# Strathim_MCU_Pin_Plan.net
KiCad netlist of a schematic drawn in Altium Designer
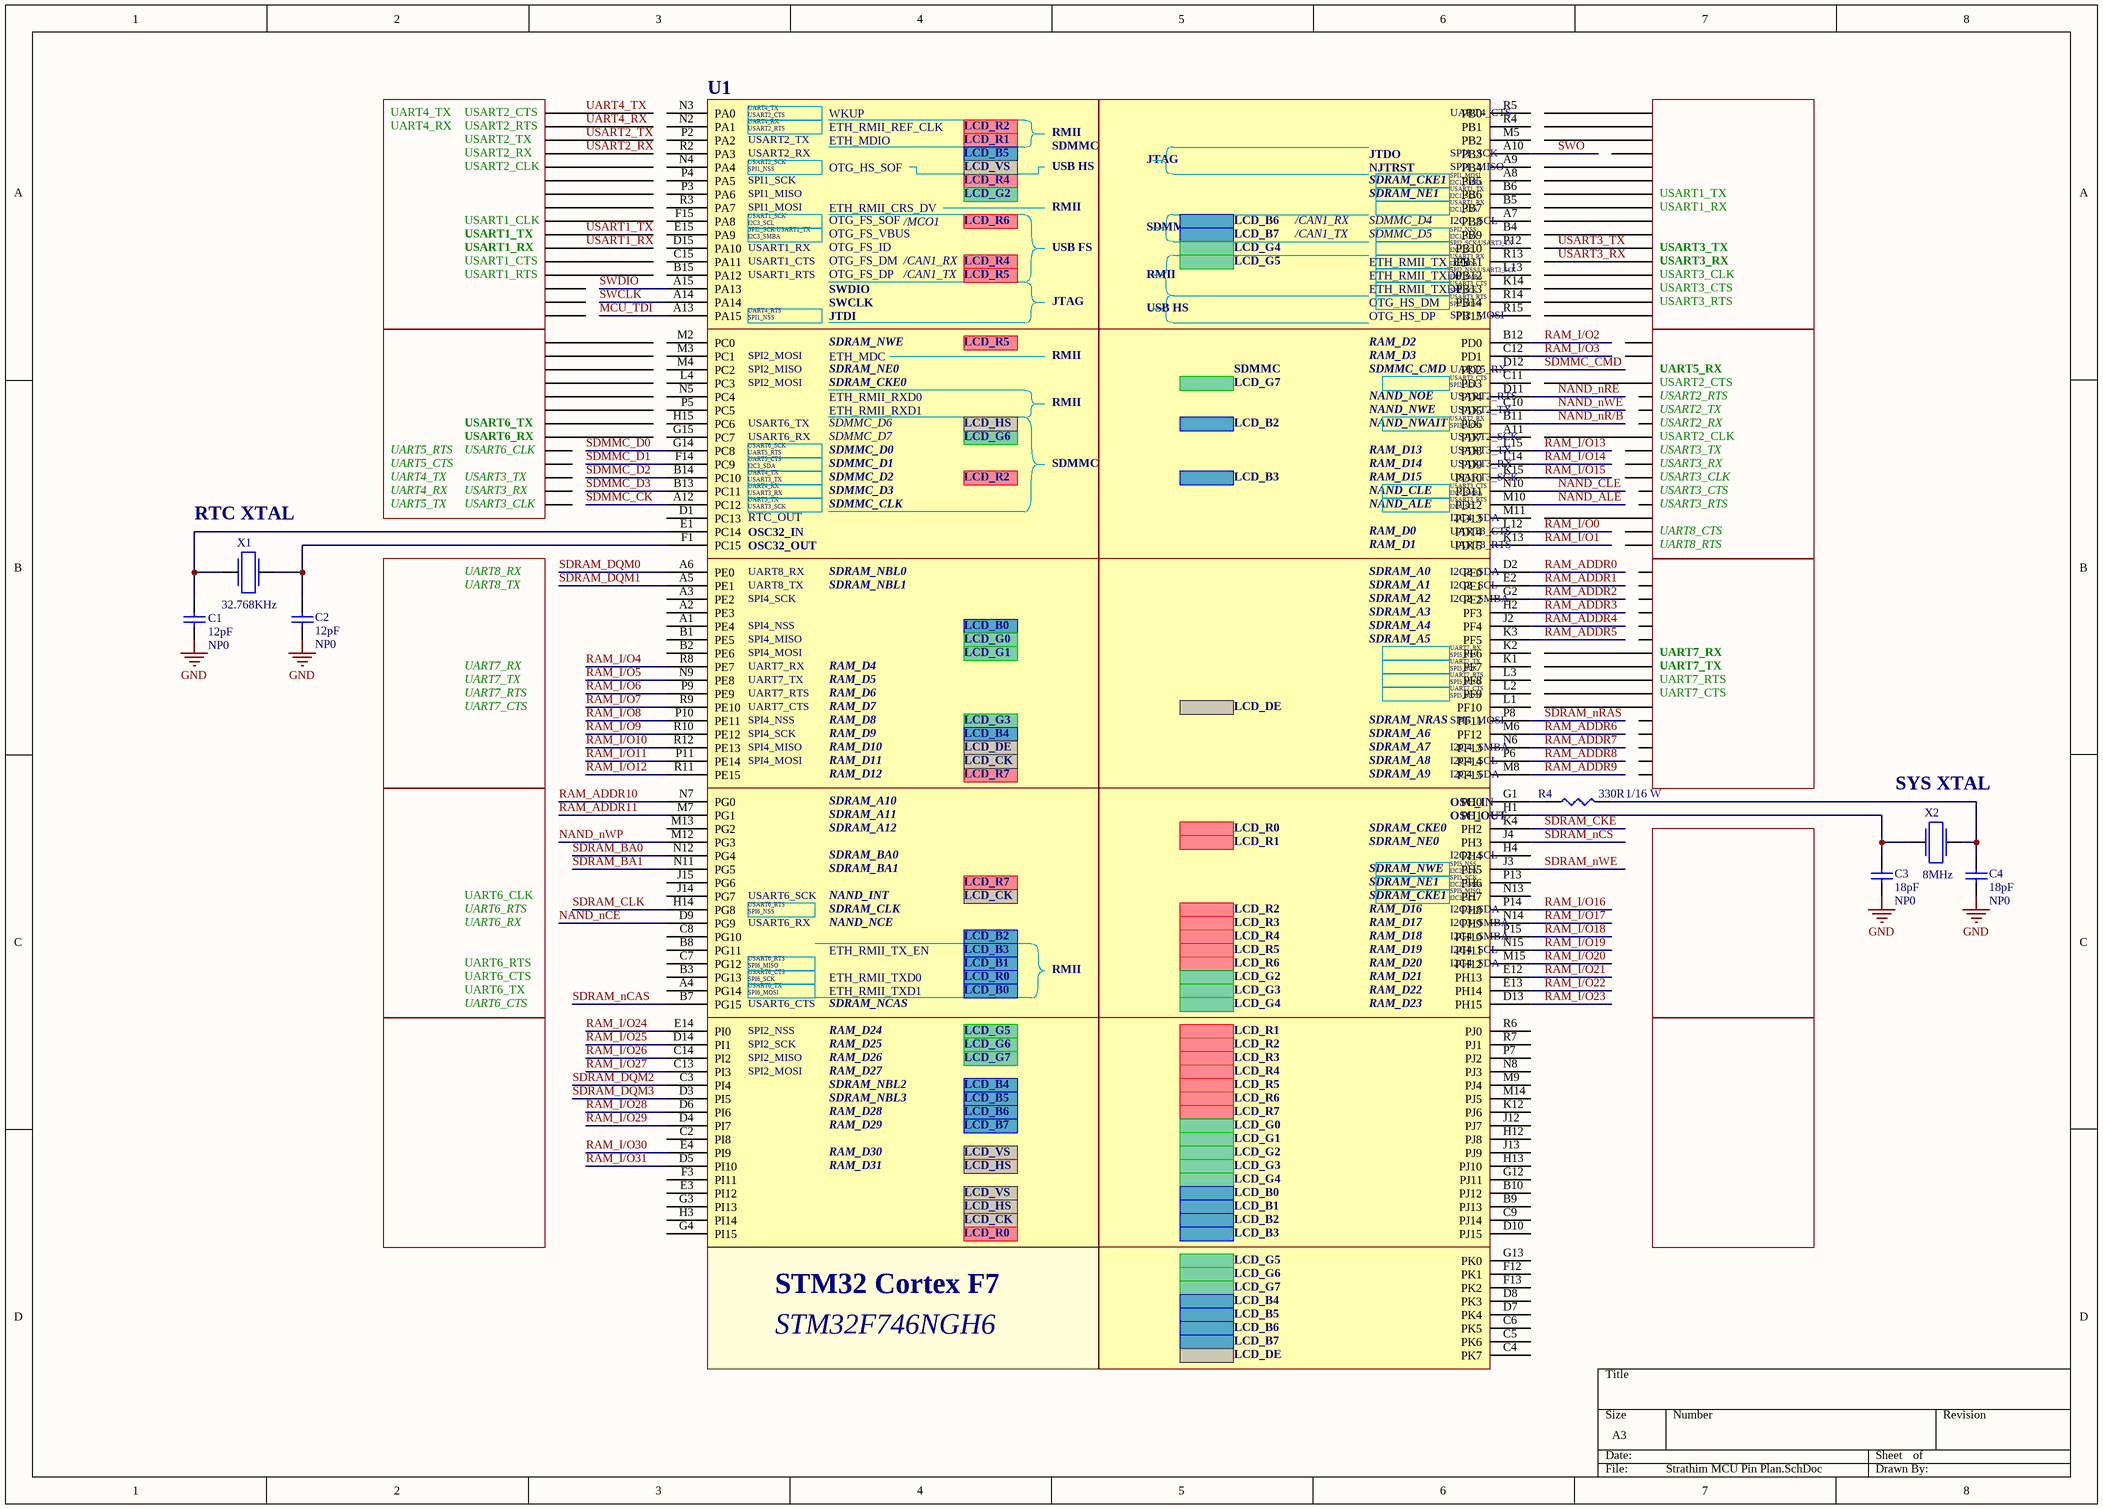
[diagram p0: Strathim MCU Pin Plan.SchDoc]

(export (version "E")
  (design (tool "Eeschema 10.0.6"))
  (components
    (comp (ref "C1")
      (value "12pF")
      (footprint "CAP0402")
      (description "Surface-mount ceramic multilayer capacitor")
      (fields (field (name "VOLTAGE") "100V") (field (name "TOLERANCE") "0.1pF") (field (name "TYPE") "NP0"))
      (libsource (lib "Capacitors") (part "ChipCap 12 NP0"))
    )
    (comp (ref "C2")
      (value "12pF")
      (footprint "CAP0402")
      (description "Surface-mount ceramic multilayer capacitor")
      (fields (field (name "VOLTAGE") "100V") (field (name "TOLERANCE") "0.1pF") (field (name "TYPE") "NP0"))
      (libsource (lib "Capacitors") (part "ChipCap 12 NP0"))
    )
    (comp (ref "C3")
      (value "18pF")
      (footprint "CAP0402")
      (description "Surface-mount ceramic multilayer capacitor")
      (fields (field (name "VOLTAGE") "100V") (field (name "TOLERANCE") "0.1pF") (field (name "TYPE") "NP0"))
      (libsource (lib "Capacitors") (part "ChipCap 18 NP0"))
    )
    (comp (ref "C4")
      (value "18pF")
      (footprint "CAP0402")
      (description "Surface-mount ceramic multilayer capacitor")
      (fields (field (name "VOLTAGE") "100V") (field (name "TOLERANCE") "0.1pF") (field (name "TYPE") "NP0"))
      (libsource (lib "Capacitors") (part "ChipCap 18 NP0"))
    )
    (comp (ref "R4")
      (value "330R")
      (footprint "RES0402")
      (description "Think Film Chip resistor")
      (fields
        (field (name "TOLERANCE") "1%")
        (field (name "MANUFACTURER PART NUMBER") "RC0402FR-07330RL (YAG)")
        (field (name "RATING") "1/16 W")
      )
      (libsource (lib "Resistors") (part "RES0402 330R 1%"))
    )
    (comp (ref "U1")
      (value "STM32F746NGH6")
      (footprint "TFBGA216")
      (description "ARM Cortex M7, 462DMIPS, 1MB Flash")
      (libsource (lib "") (part "STM32F746NGH6_1"))
    )
    (comp (ref "X1")
      (value "32.768KHz")
      (footprint "Common Devices:KX-327NHT")
      (description "Quartz crystall oscillator")
      (fields (field (name "Comment") "XTAL"))
      (libsource (lib "Common Devices") (part "Crystall oscillator"))
    )
    (comp (ref "X2")
      (value "8MHz")
      (footprint "Common Devices:ABM3 Ceramic Crystal")
      (description "Quartz crystall oscillator")
      (fields (field (name "Comment") "XTAL"))
      (libsource (lib "Common Devices") (part "ABM3 Ceramic SMD Crystal"))
    )
  )
  (nets
    (net (code "1") (name "/MCU_TDI") (class "Default")
      (node (ref "U1") (pin "A13") (pinfunction "PA15_A13") (pintype "passive"))
    )
    (net (code "2") (name "/NAND_ALE") (class "Default")
      (node (ref "U1") (pin "M10") (pinfunction "PD12_M10") (pintype "passive"))
    )
    (net (code "3") (name "/NAND_CLE") (class "Default")
      (node (ref "U1") (pin "N10") (pinfunction "PD11_N10") (pintype "passive"))
    )
    (net (code "4") (name "/NAND_nCE") (class "Default")
      (node (ref "U1") (pin "D9") (pinfunction "PG9_D9") (pintype "passive"))
    )
    (net (code "5") (name "/NAND_nRE") (class "Default")
      (node (ref "U1") (pin "D11") (pinfunction "PD4_D11") (pintype "passive"))
    )
    (net (code "6") (name "/NAND_nR{slash}B") (class "Default")
      (node (ref "U1") (pin "B11") (pinfunction "PD6_B11") (pintype "passive"))
    )
    (net (code "7") (name "/NAND_nWE") (class "Default")
      (node (ref "U1") (pin "C10") (pinfunction "PD5_C10") (pintype "passive"))
    )
    (net (code "8") (name "/NAND_nWP") (class "Default")
      (node (ref "U1") (pin "M12") (pinfunction "PG3_M12") (pintype "passive"))
    )
    (net (code "9") (name "/RAM_ADDR0") (class "Default")
      (node (ref "U1") (pin "D2") (pinfunction "PF0_D2") (pintype "passive"))
    )
    (net (code "10") (name "/RAM_ADDR1") (class "Default")
      (node (ref "U1") (pin "E2") (pinfunction "PF1_E2") (pintype "passive"))
    )
    (net (code "11") (name "/RAM_ADDR2") (class "Default")
      (node (ref "U1") (pin "G2") (pinfunction "PF2_G2") (pintype "passive"))
    )
    (net (code "12") (name "/RAM_ADDR3") (class "Default")
      (node (ref "U1") (pin "H2") (pinfunction "PF3_H2") (pintype "passive"))
    )
    (net (code "13") (name "/RAM_ADDR4") (class "Default")
      (node (ref "U1") (pin "J2") (pinfunction "PF4_J2") (pintype "passive"))
    )
    (net (code "14") (name "/RAM_ADDR5") (class "Default")
      (node (ref "U1") (pin "K3") (pinfunction "PF5_K3") (pintype "passive"))
    )
    (net (code "15") (name "/RAM_ADDR6") (class "Default")
      (node (ref "U1") (pin "M6") (pinfunction "PF12_M6") (pintype "passive"))
    )
    (net (code "16") (name "/RAM_ADDR7") (class "Default")
      (node (ref "U1") (pin "N6") (pinfunction "PF13_N6") (pintype "passive"))
    )
    (net (code "17") (name "/RAM_ADDR8") (class "Default")
      (node (ref "U1") (pin "P6") (pinfunction "PF14_P6") (pintype "passive"))
    )
    (net (code "18") (name "/RAM_ADDR9") (class "Default")
      (node (ref "U1") (pin "M8") (pinfunction "PF15_M8") (pintype "passive"))
    )
    (net (code "19") (name "/RAM_ADDR10") (class "Default")
      (node (ref "U1") (pin "N7") (pinfunction "PG0_N7") (pintype "passive"))
    )
    (net (code "20") (name "/RAM_ADDR11") (class "Default")
      (node (ref "U1") (pin "M7") (pinfunction "PG1_M7") (pintype "passive"))
    )
    (net (code "21") (name "/RAM_I{slash}O0") (class "Default")
      (node (ref "U1") (pin "L12") (pinfunction "PD14_L12") (pintype "passive"))
    )
    (net (code "22") (name "/RAM_I{slash}O1") (class "Default")
      (node (ref "U1") (pin "K13") (pinfunction "PD15_K13") (pintype "passive"))
    )
    (net (code "23") (name "/RAM_I{slash}O2") (class "Default")
      (node (ref "U1") (pin "B12") (pinfunction "PD0_B12") (pintype "passive"))
    )
    (net (code "24") (name "/RAM_I{slash}O3") (class "Default")
      (node (ref "U1") (pin "C12") (pinfunction "PD1_C12") (pintype "passive"))
    )
    (net (code "25") (name "/RAM_I{slash}O4") (class "Default")
      (node (ref "U1") (pin "R8") (pinfunction "PE7_R8") (pintype "passive"))
    )
    (net (code "26") (name "/RAM_I{slash}O5") (class "Default")
      (node (ref "U1") (pin "N9") (pinfunction "PE8_N9") (pintype "passive"))
    )
    (net (code "27") (name "/RAM_I{slash}O6") (class "Default")
      (node (ref "U1") (pin "P9") (pinfunction "PE9_P9") (pintype "passive"))
    )
    (net (code "28") (name "/RAM_I{slash}O7") (class "Default")
      (node (ref "U1") (pin "R9") (pinfunction "PE10_R9") (pintype "passive"))
    )
    (net (code "29") (name "/RAM_I{slash}O8") (class "Default")
      (node (ref "U1") (pin "P10") (pinfunction "PE11_P10") (pintype "passive"))
    )
    (net (code "30") (name "/RAM_I{slash}O9") (class "Default")
      (node (ref "U1") (pin "R10") (pinfunction "PE12_R10") (pintype "passive"))
    )
    (net (code "31") (name "/RAM_I{slash}O10") (class "Default")
      (node (ref "U1") (pin "R12") (pinfunction "PE13_R12") (pintype "passive"))
    )
    (net (code "32") (name "/RAM_I{slash}O11") (class "Default")
      (node (ref "U1") (pin "P11") (pinfunction "PE14_P11") (pintype "passive"))
    )
    (net (code "33") (name "/RAM_I{slash}O12") (class "Default")
      (node (ref "U1") (pin "R11") (pinfunction "PE15_R11") (pintype "passive"))
    )
    (net (code "34") (name "/RAM_I{slash}O13") (class "Default")
      (node (ref "U1") (pin "L15") (pinfunction "PD8_L15") (pintype "passive"))
    )
    (net (code "35") (name "/RAM_I{slash}O14") (class "Default")
      (node (ref "U1") (pin "L14") (pinfunction "PD9_L14") (pintype "passive"))
    )
    (net (code "36") (name "/RAM_I{slash}O15") (class "Default")
      (node (ref "U1") (pin "K15") (pinfunction "PD10_K15") (pintype "passive"))
    )
    (net (code "37") (name "/RAM_I{slash}O16") (class "Default")
      (node (ref "U1") (pin "P14") (pinfunction "PH8_P14") (pintype "passive"))
    )
    (net (code "38") (name "/RAM_I{slash}O17") (class "Default")
      (node (ref "U1") (pin "N14") (pinfunction "PH9_N14") (pintype "passive"))
    )
    (net (code "39") (name "/RAM_I{slash}O18") (class "Default")
      (node (ref "U1") (pin "P15") (pinfunction "PH10_P15") (pintype "passive"))
    )
    (net (code "40") (name "/RAM_I{slash}O19") (class "Default")
      (node (ref "U1") (pin "N15") (pinfunction "PH11_N15") (pintype "passive"))
    )
    (net (code "41") (name "/RAM_I{slash}O20") (class "Default")
      (node (ref "U1") (pin "M15") (pinfunction "PH12_M15") (pintype "passive"))
    )
    (net (code "42") (name "/RAM_I{slash}O21") (class "Default")
      (node (ref "U1") (pin "E12") (pinfunction "PH13_E12") (pintype "passive"))
    )
    (net (code "43") (name "/RAM_I{slash}O22") (class "Default")
      (node (ref "U1") (pin "E13") (pinfunction "PH14_E13") (pintype "passive"))
    )
    (net (code "44") (name "/RAM_I{slash}O23") (class "Default")
      (node (ref "U1") (pin "D13") (pinfunction "PH15_D13") (pintype "passive"))
    )
    (net (code "45") (name "/RAM_I{slash}O24") (class "Default")
      (node (ref "U1") (pin "E14") (pinfunction "PI0_E14") (pintype "passive"))
    )
    (net (code "46") (name "/RAM_I{slash}O25") (class "Default")
      (node (ref "U1") (pin "D14") (pinfunction "PI1_D14") (pintype "passive"))
    )
    (net (code "47") (name "/RAM_I{slash}O26") (class "Default")
      (node (ref "U1") (pin "C14") (pinfunction "PI2_C14") (pintype "passive"))
    )
    (net (code "48") (name "/RAM_I{slash}O27") (class "Default")
      (node (ref "U1") (pin "C13") (pinfunction "PI3_C13") (pintype "passive"))
    )
    (net (code "49") (name "/RAM_I{slash}O28") (class "Default")
      (node (ref "U1") (pin "D6") (pinfunction "PI6_D6") (pintype "passive"))
    )
    (net (code "50") (name "/RAM_I{slash}O29") (class "Default")
      (node (ref "U1") (pin "D4") (pinfunction "PI7_D4") (pintype "passive"))
    )
    (net (code "51") (name "/RAM_I{slash}O30") (class "Default")
      (node (ref "U1") (pin "E4") (pinfunction "PI9_E4") (pintype "passive"))
    )
    (net (code "52") (name "/RAM_I{slash}O31") (class "Default")
      (node (ref "U1") (pin "D5") (pinfunction "PI10_D5") (pintype "passive"))
    )
    (net (code "53") (name "/SDMMC_CK") (class "Default")
      (node (ref "U1") (pin "A12") (pinfunction "PC12_A12") (pintype "passive"))
    )
    (net (code "54") (name "/SDMMC_CMD") (class "Default")
      (node (ref "U1") (pin "D12") (pinfunction "PD2_D12") (pintype "passive"))
    )
    (net (code "55") (name "/SDMMC_D0") (class "Default")
      (node (ref "U1") (pin "G14") (pinfunction "PC8_G14") (pintype "passive"))
    )
    (net (code "56") (name "/SDMMC_D1") (class "Default")
      (node (ref "U1") (pin "F14") (pinfunction "PC9_F14") (pintype "passive"))
    )
    (net (code "57") (name "/SDMMC_D2") (class "Default")
      (node (ref "U1") (pin "B14") (pinfunction "PC10_B14") (pintype "passive"))
    )
    (net (code "58") (name "/SDMMC_D3") (class "Default")
      (node (ref "U1") (pin "B13") (pinfunction "PC11_B13") (pintype "passive"))
    )
    (net (code "59") (name "/SDRAM_BA0") (class "Default")
      (node (ref "U1") (pin "N12") (pinfunction "PG4_N12") (pintype "passive"))
    )
    (net (code "60") (name "/SDRAM_BA1") (class "Default")
      (node (ref "U1") (pin "N11") (pinfunction "PG5_N11") (pintype "passive"))
    )
    (net (code "61") (name "/SDRAM_CKE") (class "Default")
      (node (ref "U1") (pin "K4") (pinfunction "PH2_K4") (pintype "passive"))
    )
    (net (code "62") (name "/SDRAM_CLK") (class "Default")
      (node (ref "U1") (pin "H14") (pinfunction "PG8_H14") (pintype "passive"))
    )
    (net (code "63") (name "/SDRAM_DQM0") (class "Default")
      (node (ref "U1") (pin "A6") (pinfunction "PE0_A6") (pintype "passive"))
    )
    (net (code "64") (name "/SDRAM_DQM1") (class "Default")
      (node (ref "U1") (pin "A5") (pinfunction "PE1_A5") (pintype "passive"))
    )
    (net (code "65") (name "/SDRAM_DQM2") (class "Default")
      (node (ref "U1") (pin "C3") (pinfunction "PI4_C3") (pintype "passive"))
    )
    (net (code "66") (name "/SDRAM_DQM3") (class "Default")
      (node (ref "U1") (pin "D3") (pinfunction "PI5_D3") (pintype "passive"))
    )
    (net (code "67") (name "/SDRAM_nCAS") (class "Default")
      (node (ref "U1") (pin "B7") (pinfunction "PG15_B7") (pintype "passive"))
    )
    (net (code "68") (name "/SDRAM_nCS") (class "Default")
      (node (ref "U1") (pin "J4") (pinfunction "PH3_J4") (pintype "passive"))
    )
    (net (code "69") (name "/SDRAM_nRAS") (class "Default")
      (node (ref "U1") (pin "P8") (pinfunction "PF11_P8") (pintype "passive"))
    )
    (net (code "70") (name "/SDRAM_nWE") (class "Default")
      (node (ref "U1") (pin "J3") (pinfunction "PH5_J3") (pintype "passive"))
    )
    (net (code "71") (name "/SWCLK") (class "Default")
      (node (ref "U1") (pin "A14") (pinfunction "PA14_A14") (pintype "passive"))
    )
    (net (code "72") (name "/SWDIO") (class "Default")
      (node (ref "U1") (pin "A15") (pinfunction "PA13_A15") (pintype "passive"))
    )
    (net (code "73") (name "/SWO") (class "Default")
      (node (ref "U1") (pin "A10") (pinfunction "PB3_A10") (pintype "passive"))
    )
    (net (code "82") (name "GND") (class "Default")
      (node (ref "C1") (pin "1") (pinfunction "1_1") (pintype "passive"))
      (node (ref "C2") (pin "1") (pinfunction "1_1") (pintype "passive"))
      (node (ref "C3") (pin "1") (pinfunction "1_1") (pintype "passive"))
      (node (ref "C4") (pin "1") (pinfunction "1_1") (pintype "passive"))
    )
    (net (code "83") (name "Net-(C4-Pad2)") (class "Default")
      (node (ref "C4") (pin "2") (pinfunction "2_2") (pintype "passive"))
      (node (ref "R4") (pin "2") (pintype "passive"))
      (node (ref "X2") (pin "2") (pinfunction "2_2") (pintype "passive"))
    )
    (net (code "84") (name "Net-(U1C-PC14)") (class "Default")
      (node (ref "C1") (pin "2") (pinfunction "2_2") (pintype "passive"))
      (node (ref "U1") (pin "E1") (pinfunction "PC14_E1") (pintype "passive"))
      (node (ref "X1") (pin "1") (pinfunction "1_1") (pintype "passive"))
    )
    (net (code "85") (name "Net-(U1C-PC15)") (class "Default")
      (node (ref "C2") (pin "2") (pinfunction "2_2") (pintype "passive"))
      (node (ref "U1") (pin "F1") (pinfunction "PC15_F1") (pintype "passive"))
      (node (ref "X1") (pin "2") (pinfunction "2_2") (pintype "passive"))
    )
    (net (code "86") (name "Net-(U1H-PH0)") (class "Default")
      (node (ref "R4") (pin "1") (pintype "passive"))
      (node (ref "U1") (pin "G1") (pinfunction "PH0_G1") (pintype "passive"))
    )
    (net (code "87") (name "Net-(U1H-PH1)") (class "Default")
      (node (ref "C3") (pin "2") (pinfunction "2_2") (pintype "passive"))
      (node (ref "U1") (pin "H1") (pinfunction "PH1_H1") (pintype "passive"))
      (node (ref "X2") (pin "1") (pinfunction "1_1") (pintype "passive"))
    )
    (net (code "88") (name "unconnected-(U1A-PA0-PadN3)") (class "Default")
      (node (ref "U1") (pin "N3") (pinfunction "PA0_N3") (pintype "passive"))
    )
    (net (code "89") (name "unconnected-(U1A-PA1-PadN2)") (class "Default")
      (node (ref "U1") (pin "N2") (pinfunction "PA1_N2") (pintype "passive"))
    )
    (net (code "90") (name "unconnected-(U1A-PA2-PadP2)") (class "Default")
      (node (ref "U1") (pin "P2") (pinfunction "PA2_P2") (pintype "passive"))
    )
    (net (code "91") (name "unconnected-(U1A-PA3-PadR2)") (class "Default")
      (node (ref "U1") (pin "R2") (pinfunction "PA3_R2") (pintype "passive"))
    )
    (net (code "92") (name "unconnected-(U1A-PA4-PadN4)") (class "Default")
      (node (ref "U1") (pin "N4") (pinfunction "PA4_N4") (pintype "passive"))
    )
    (net (code "93") (name "unconnected-(U1A-PA5-PadP4)") (class "Default")
      (node (ref "U1") (pin "P4") (pinfunction "PA5_P4") (pintype "passive"))
    )
    (net (code "94") (name "unconnected-(U1A-PA6-PadP3)") (class "Default")
      (node (ref "U1") (pin "P3") (pinfunction "PA6_P3") (pintype "passive"))
    )
    (net (code "95") (name "unconnected-(U1A-PA7-PadR3)") (class "Default")
      (node (ref "U1") (pin "R3") (pinfunction "PA7_R3") (pintype "passive"))
    )
    (net (code "96") (name "unconnected-(U1A-PA8-PadF15)") (class "Default")
      (node (ref "U1") (pin "F15") (pinfunction "PA8_F15") (pintype "passive"))
    )
    (net (code "97") (name "unconnected-(U1A-PA9-PadE15)") (class "Default")
      (node (ref "U1") (pin "E15") (pinfunction "PA9_E15") (pintype "passive"))
    )
    (net (code "98") (name "unconnected-(U1A-PA10-PadD15)") (class "Default")
      (node (ref "U1") (pin "D15") (pinfunction "PA10_D15") (pintype "passive"))
    )
    (net (code "99") (name "unconnected-(U1A-PA11-PadC15)") (class "Default")
      (node (ref "U1") (pin "C15") (pinfunction "PA11_C15") (pintype "passive"))
    )
    (net (code "100") (name "unconnected-(U1A-PA12-PadB15)") (class "Default")
      (node (ref "U1") (pin "B15") (pinfunction "PA12_B15") (pintype "passive"))
    )
    (net (code "101") (name "unconnected-(U1B-PB0-PadR5)") (class "Default")
      (node (ref "U1") (pin "R5") (pinfunction "PB0_R5") (pintype "passive"))
    )
    (net (code "102") (name "unconnected-(U1B-PB1-PadR4)") (class "Default")
      (node (ref "U1") (pin "R4") (pinfunction "PB1_R4") (pintype "passive"))
    )
    (net (code "103") (name "unconnected-(U1B-PB2-PadM5)") (class "Default")
      (node (ref "U1") (pin "M5") (pinfunction "PB2_M5") (pintype "passive"))
    )
    (net (code "104") (name "unconnected-(U1B-PB4-PadA9)") (class "Default")
      (node (ref "U1") (pin "A9") (pinfunction "PB4_A9") (pintype "passive"))
    )
    (net (code "105") (name "unconnected-(U1B-PB5-PadA8)") (class "Default")
      (node (ref "U1") (pin "A8") (pinfunction "PB5_A8") (pintype "passive"))
    )
    (net (code "106") (name "unconnected-(U1B-PB6-PadB6)") (class "Default")
      (node (ref "U1") (pin "B6") (pinfunction "PB6_B6") (pintype "passive"))
    )
    (net (code "107") (name "unconnected-(U1B-PB7-PadB5)") (class "Default")
      (node (ref "U1") (pin "B5") (pinfunction "PB7_B5") (pintype "passive"))
    )
    (net (code "108") (name "unconnected-(U1B-PB8-PadA7)") (class "Default")
      (node (ref "U1") (pin "A7") (pinfunction "PB8_A7") (pintype "passive"))
    )
    (net (code "109") (name "unconnected-(U1B-PB9-PadB4)") (class "Default")
      (node (ref "U1") (pin "B4") (pinfunction "PB9_B4") (pintype "passive"))
    )
    (net (code "110") (name "unconnected-(U1B-PB10-PadP12)") (class "Default")
      (node (ref "U1") (pin "P12") (pinfunction "PB10_P12") (pintype "passive"))
    )
    (net (code "111") (name "unconnected-(U1B-PB11-PadR13)") (class "Default")
      (node (ref "U1") (pin "R13") (pinfunction "PB11_R13") (pintype "passive"))
    )
    (net (code "112") (name "unconnected-(U1B-PB12-PadL13)") (class "Default")
      (node (ref "U1") (pin "L13") (pinfunction "PB12_L13") (pintype "passive"))
    )
    (net (code "113") (name "unconnected-(U1B-PB13-PadK14)") (class "Default")
      (node (ref "U1") (pin "K14") (pinfunction "PB13_K14") (pintype "passive"))
    )
    (net (code "114") (name "unconnected-(U1B-PB14-PadR14)") (class "Default")
      (node (ref "U1") (pin "R14") (pinfunction "PB14_R14") (pintype "passive"))
    )
    (net (code "115") (name "unconnected-(U1B-PB15-PadR15)") (class "Default")
      (node (ref "U1") (pin "R15") (pinfunction "PB15_R15") (pintype "passive"))
    )
    (net (code "116") (name "unconnected-(U1C-PC0-PadM2)") (class "Default")
      (node (ref "U1") (pin "M2") (pinfunction "PC0_M2") (pintype "passive"))
    )
    (net (code "117") (name "unconnected-(U1C-PC1-PadM3)") (class "Default")
      (node (ref "U1") (pin "M3") (pinfunction "PC1_M3") (pintype "passive"))
    )
    (net (code "118") (name "unconnected-(U1C-PC2-PadM4)") (class "Default")
      (node (ref "U1") (pin "M4") (pinfunction "PC2_M4") (pintype "passive"))
    )
    (net (code "119") (name "unconnected-(U1C-PC3-PadL4)") (class "Default")
      (node (ref "U1") (pin "L4") (pinfunction "PC3_L4") (pintype "passive"))
    )
    (net (code "120") (name "unconnected-(U1C-PC4-PadN5)") (class "Default")
      (node (ref "U1") (pin "N5") (pinfunction "PC4_N5") (pintype "passive"))
    )
    (net (code "121") (name "unconnected-(U1C-PC5-PadP5)") (class "Default")
      (node (ref "U1") (pin "P5") (pinfunction "PC5_P5") (pintype "passive"))
    )
    (net (code "122") (name "unconnected-(U1C-PC6-PadH15)") (class "Default")
      (node (ref "U1") (pin "H15") (pinfunction "PC6_H15") (pintype "passive"))
    )
    (net (code "123") (name "unconnected-(U1C-PC7-PadG15)") (class "Default")
      (node (ref "U1") (pin "G15") (pinfunction "PC7_G15") (pintype "passive"))
    )
    (net (code "124") (name "unconnected-(U1C-PC13-PadD1)") (class "Default")
      (node (ref "U1") (pin "D1") (pinfunction "PC13_D1") (pintype "passive"))
    )
    (net (code "125") (name "unconnected-(U1D-PD3-PadC11)") (class "Default")
      (node (ref "U1") (pin "C11") (pinfunction "PD3_C11") (pintype "passive"))
    )
    (net (code "126") (name "unconnected-(U1D-PD7-PadA11)") (class "Default")
      (node (ref "U1") (pin "A11") (pinfunction "PD7_A11") (pintype "passive"))
    )
    (net (code "127") (name "unconnected-(U1D-PD13-PadM11)") (class "Default")
      (node (ref "U1") (pin "M11") (pinfunction "PD13_M11") (pintype "passive"))
    )
    (net (code "128") (name "unconnected-(U1E-PE2-PadA3)") (class "Default")
      (node (ref "U1") (pin "A3") (pinfunction "PE2_A3") (pintype "passive"))
    )
    (net (code "129") (name "unconnected-(U1E-PE3-PadA2)") (class "Default")
      (node (ref "U1") (pin "A2") (pinfunction "PE3_A2") (pintype "passive"))
    )
    (net (code "130") (name "unconnected-(U1E-PE4-PadA1)") (class "Default")
      (node (ref "U1") (pin "A1") (pinfunction "PE4_A1") (pintype "passive"))
    )
    (net (code "131") (name "unconnected-(U1E-PE5-PadB1)") (class "Default")
      (node (ref "U1") (pin "B1") (pinfunction "PE5_B1") (pintype "passive"))
    )
    (net (code "132") (name "unconnected-(U1E-PE6-PadB2)") (class "Default")
      (node (ref "U1") (pin "B2") (pinfunction "PE6_B2") (pintype "passive"))
    )
    (net (code "133") (name "unconnected-(U1F-PF6-PadK2)") (class "Default")
      (node (ref "U1") (pin "K2") (pinfunction "PF6_K2") (pintype "passive"))
    )
    (net (code "134") (name "unconnected-(U1F-PF7-PadK1)") (class "Default")
      (node (ref "U1") (pin "K1") (pinfunction "PF7_K1") (pintype "passive"))
    )
    (net (code "135") (name "unconnected-(U1F-PF8-PadL3)") (class "Default")
      (node (ref "U1") (pin "L3") (pinfunction "PF8_L3") (pintype "passive"))
    )
    (net (code "136") (name "unconnected-(U1F-PF9-PadL2)") (class "Default")
      (node (ref "U1") (pin "L2") (pinfunction "PF9_L2") (pintype "passive"))
    )
    (net (code "137") (name "unconnected-(U1F-PF10-PadL1)") (class "Default")
      (node (ref "U1") (pin "L1") (pinfunction "PF10_L1") (pintype "passive"))
    )
    (net (code "138") (name "unconnected-(U1G-PG2-PadM13)") (class "Default")
      (node (ref "U1") (pin "M13") (pinfunction "PG2_M13") (pintype "passive"))
    )
    (net (code "139") (name "unconnected-(U1G-PG6-PadJ15)") (class "Default")
      (node (ref "U1") (pin "J15") (pinfunction "PG6_J15") (pintype "passive"))
    )
    (net (code "140") (name "unconnected-(U1G-PG7-PadJ14)") (class "Default")
      (node (ref "U1") (pin "J14") (pinfunction "PG7_J14") (pintype "passive"))
    )
    (net (code "141") (name "unconnected-(U1G-PG10-PadC8)") (class "Default")
      (node (ref "U1") (pin "C8") (pinfunction "PG10_C8") (pintype "passive"))
    )
    (net (code "142") (name "unconnected-(U1G-PG11-PadB8)") (class "Default")
      (node (ref "U1") (pin "B8") (pinfunction "PG11_B8") (pintype "passive"))
    )
    (net (code "143") (name "unconnected-(U1G-PG12-PadC7)") (class "Default")
      (node (ref "U1") (pin "C7") (pinfunction "PG12_C7") (pintype "passive"))
    )
    (net (code "144") (name "unconnected-(U1G-PG13-PadB3)") (class "Default")
      (node (ref "U1") (pin "B3") (pinfunction "PG13_B3") (pintype "passive"))
    )
    (net (code "145") (name "unconnected-(U1G-PG14-PadA4)") (class "Default")
      (node (ref "U1") (pin "A4") (pinfunction "PG14_A4") (pintype "passive"))
    )
    (net (code "146") (name "unconnected-(U1H-PH4-PadH4)") (class "Default")
      (node (ref "U1") (pin "H4") (pinfunction "PH4_H4") (pintype "passive"))
    )
    (net (code "147") (name "unconnected-(U1H-PH6-PadP13)") (class "Default")
      (node (ref "U1") (pin "P13") (pinfunction "PH6_P13") (pintype "passive"))
    )
    (net (code "148") (name "unconnected-(U1H-PH7-PadN13)") (class "Default")
      (node (ref "U1") (pin "N13") (pinfunction "PH7_N13") (pintype "passive"))
    )
    (net (code "149") (name "unconnected-(U1I-PI8-PadC2)") (class "Default")
      (node (ref "U1") (pin "C2") (pinfunction "PI8_C2") (pintype "passive"))
    )
    (net (code "150") (name "unconnected-(U1I-PI11-PadF3)") (class "Default")
      (node (ref "U1") (pin "F3") (pinfunction "PI11_F3") (pintype "passive"))
    )
    (net (code "151") (name "unconnected-(U1I-PI12-PadE3)") (class "Default")
      (node (ref "U1") (pin "E3") (pinfunction "PI12_E3") (pintype "passive"))
    )
    (net (code "152") (name "unconnected-(U1I-PI13-PadG3)") (class "Default")
      (node (ref "U1") (pin "G3") (pinfunction "PI13_G3") (pintype "passive"))
    )
    (net (code "153") (name "unconnected-(U1I-PI14-PadH3)") (class "Default")
      (node (ref "U1") (pin "H3") (pinfunction "PI14_H3") (pintype "passive"))
    )
    (net (code "154") (name "unconnected-(U1I-PI15-PadG4)") (class "Default")
      (node (ref "U1") (pin "G4") (pinfunction "PI15_G4") (pintype "passive"))
    )
    (net (code "155") (name "unconnected-(U1J-PJ0-PadR6)") (class "Default")
      (node (ref "U1") (pin "R6") (pinfunction "PJ0_R6") (pintype "passive"))
    )
    (net (code "156") (name "unconnected-(U1J-PJ1-PadR7)") (class "Default")
      (node (ref "U1") (pin "R7") (pinfunction "PJ1_R7") (pintype "passive"))
    )
    (net (code "157") (name "unconnected-(U1J-PJ2-PadP7)") (class "Default")
      (node (ref "U1") (pin "P7") (pinfunction "PJ2_P7") (pintype "passive"))
    )
    (net (code "158") (name "unconnected-(U1J-PJ3-PadN8)") (class "Default")
      (node (ref "U1") (pin "N8") (pinfunction "PJ3_N8") (pintype "passive"))
    )
    (net (code "159") (name "unconnected-(U1J-PJ4-PadM9)") (class "Default")
      (node (ref "U1") (pin "M9") (pinfunction "PJ4_M9") (pintype "passive"))
    )
    (net (code "160") (name "unconnected-(U1J-PJ5-PadM14)") (class "Default")
      (node (ref "U1") (pin "M14") (pinfunction "PJ5_M14") (pintype "passive"))
    )
    (net (code "161") (name "unconnected-(U1J-PJ6-PadK12)") (class "Default")
      (node (ref "U1") (pin "K12") (pinfunction "PJ6_K12") (pintype "passive"))
    )
    (net (code "162") (name "unconnected-(U1J-PJ7-PadJ12)") (class "Default")
      (node (ref "U1") (pin "J12") (pinfunction "PJ7_J12") (pintype "passive"))
    )
    (net (code "163") (name "unconnected-(U1J-PJ8-PadH12)") (class "Default")
      (node (ref "U1") (pin "H12") (pinfunction "PJ8_H12") (pintype "passive"))
    )
    (net (code "164") (name "unconnected-(U1J-PJ9-PadJ13)") (class "Default")
      (node (ref "U1") (pin "J13") (pinfunction "PJ9_J13") (pintype "passive"))
    )
    (net (code "165") (name "unconnected-(U1J-PJ10-PadH13)") (class "Default")
      (node (ref "U1") (pin "H13") (pinfunction "PJ10_H13") (pintype "passive"))
    )
    (net (code "166") (name "unconnected-(U1J-PJ11-PadG12)") (class "Default")
      (node (ref "U1") (pin "G12") (pinfunction "PJ11_G12") (pintype "passive"))
    )
    (net (code "167") (name "unconnected-(U1J-PJ12-PadB10)") (class "Default")
      (node (ref "U1") (pin "B10") (pinfunction "PJ12_B10") (pintype "passive"))
    )
    (net (code "168") (name "unconnected-(U1J-PJ13-PadB9)") (class "Default")
      (node (ref "U1") (pin "B9") (pinfunction "PJ13_B9") (pintype "passive"))
    )
    (net (code "169") (name "unconnected-(U1J-PJ14-PadC9)") (class "Default")
      (node (ref "U1") (pin "C9") (pinfunction "PJ14_C9") (pintype "passive"))
    )
    (net (code "170") (name "unconnected-(U1J-PJ15-PadD10)") (class "Default")
      (node (ref "U1") (pin "D10") (pinfunction "PJ15_D10") (pintype "passive"))
    )
    (net (code "171") (name "unconnected-(U1K-PK0-PadG13)") (class "Default")
      (node (ref "U1") (pin "G13") (pinfunction "PK0_G13") (pintype "passive"))
    )
    (net (code "172") (name "unconnected-(U1K-PK1-PadF12)") (class "Default")
      (node (ref "U1") (pin "F12") (pinfunction "PK1_F12") (pintype "passive"))
    )
    (net (code "173") (name "unconnected-(U1K-PK2-PadF13)") (class "Default")
      (node (ref "U1") (pin "F13") (pinfunction "PK2_F13") (pintype "passive"))
    )
    (net (code "174") (name "unconnected-(U1K-PK3-PadD8)") (class "Default")
      (node (ref "U1") (pin "D8") (pinfunction "PK3_D8") (pintype "passive"))
    )
    (net (code "175") (name "unconnected-(U1K-PK4-PadD7)") (class "Default")
      (node (ref "U1") (pin "D7") (pinfunction "PK4_D7") (pintype "passive"))
    )
    (net (code "176") (name "unconnected-(U1K-PK5-PadC6)") (class "Default")
      (node (ref "U1") (pin "C6") (pinfunction "PK5_C6") (pintype "passive"))
    )
    (net (code "177") (name "unconnected-(U1K-PK6-PadC5)") (class "Default")
      (node (ref "U1") (pin "C5") (pinfunction "PK6_C5") (pintype "passive"))
    )
    (net (code "178") (name "unconnected-(U1K-PK7-PadC4)") (class "Default")
      (node (ref "U1") (pin "C4") (pinfunction "PK7_C4") (pintype "passive"))
    )
  )
)
